# 04-ModuleControls.net
KiCad netlist of a schematic drawn in Altium Designer
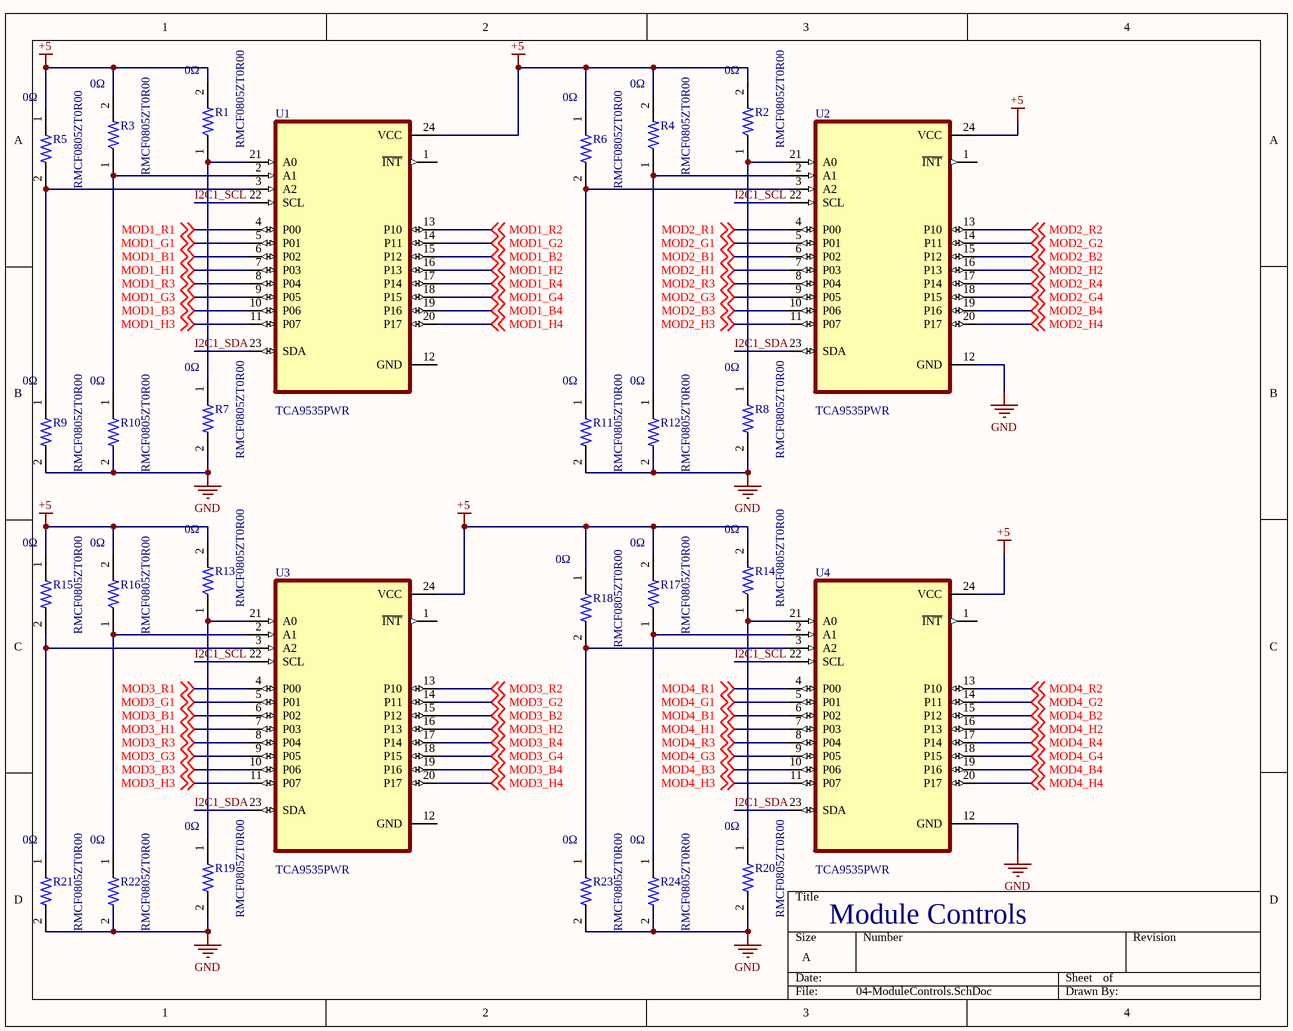
[diagram p0: 04-ModuleControls.SchDoc]

(export (version "E")
  (design (tool "Eeschema 10.0.6"))
  (components
    (comp (ref "R1")
      (value "RMCF0805ZT0R00")
      (footprint "RESC2012X60N")
      (description "0 Ohms Jumper 0.125W, 1/8W Chip Resistor 0805 (2012 Metric) Automotive AEC-Q200 Thick Film")
      (fields (field (name "MF") "Stackpole Electronics") (field (name "RESITANCE") "0Ω"))
      (libsource (lib "base-board") (part "RMCF0805ZT0R00"))
    )
    (comp (ref "R2")
      (value "RMCF0805ZT0R00")
      (footprint "RESC2012X60N")
      (description "0 Ohms Jumper 0.125W, 1/8W Chip Resistor 0805 (2012 Metric) Automotive AEC-Q200 Thick Film")
      (fields (field (name "MF") "Stackpole Electronics") (field (name "RESITANCE") "0Ω"))
      (libsource (lib "base-board") (part "RMCF0805ZT0R00"))
    )
    (comp (ref "R3")
      (value "RMCF0805ZT0R00")
      (footprint "RESC2012X60N")
      (description "0 Ohms Jumper 0.125W, 1/8W Chip Resistor 0805 (2012 Metric) Automotive AEC-Q200 Thick Film")
      (fields (field (name "MF") "Stackpole Electronics") (field (name "RESITANCE") "0Ω"))
      (libsource (lib "base-board") (part "RMCF0805ZT0R00"))
    )
    (comp (ref "R4")
      (value "RMCF0805ZT0R00")
      (footprint "RESC2012X60N")
      (description "0 Ohms Jumper 0.125W, 1/8W Chip Resistor 0805 (2012 Metric) Automotive AEC-Q200 Thick Film")
      (fields (field (name "MF") "Stackpole Electronics") (field (name "RESITANCE") "0Ω"))
      (libsource (lib "base-board") (part "RMCF0805ZT0R00"))
    )
    (comp (ref "R5")
      (value "RMCF0805ZT0R00")
      (footprint "RESC2012X60N")
      (description "0 Ohms Jumper 0.125W, 1/8W Chip Resistor 0805 (2012 Metric) Automotive AEC-Q200 Thick Film")
      (fields (field (name "MF") "Stackpole Electronics") (field (name "RESITANCE") "0Ω"))
      (libsource (lib "base-board") (part "RMCF0805ZT0R00"))
    )
    (comp (ref "R6")
      (value "RMCF0805ZT0R00")
      (footprint "RESC2012X60N")
      (description "0 Ohms Jumper 0.125W, 1/8W Chip Resistor 0805 (2012 Metric) Automotive AEC-Q200 Thick Film")
      (fields (field (name "MF") "Stackpole Electronics") (field (name "RESITANCE") "0Ω"))
      (libsource (lib "base-board") (part "RMCF0805ZT0R00"))
    )
    (comp (ref "R7")
      (value "RMCF0805ZT0R00")
      (footprint "RESC2012X60N")
      (description "0 Ohms Jumper 0.125W, 1/8W Chip Resistor 0805 (2012 Metric) Automotive AEC-Q200 Thick Film")
      (fields (field (name "MF") "Stackpole Electronics") (field (name "RESITANCE") "0Ω"))
      (libsource (lib "base-board") (part "RMCF0805ZT0R00"))
    )
    (comp (ref "R8")
      (value "RMCF0805ZT0R00")
      (footprint "RESC2012X60N")
      (description "0 Ohms Jumper 0.125W, 1/8W Chip Resistor 0805 (2012 Metric) Automotive AEC-Q200 Thick Film")
      (fields (field (name "MF") "Stackpole Electronics") (field (name "RESITANCE") "0Ω"))
      (libsource (lib "base-board") (part "RMCF0805ZT0R00"))
    )
    (comp (ref "R9")
      (value "RMCF0805ZT0R00")
      (footprint "RESC2012X60N")
      (description "0 Ohms Jumper 0.125W, 1/8W Chip Resistor 0805 (2012 Metric) Automotive AEC-Q200 Thick Film")
      (fields (field (name "MF") "Stackpole Electronics") (field (name "RESITANCE") "0Ω"))
      (libsource (lib "base-board") (part "RMCF0805ZT0R00"))
    )
    (comp (ref "R10")
      (value "RMCF0805ZT0R00")
      (footprint "RESC2012X60N")
      (description "0 Ohms Jumper 0.125W, 1/8W Chip Resistor 0805 (2012 Metric) Automotive AEC-Q200 Thick Film")
      (fields (field (name "MF") "Stackpole Electronics") (field (name "RESITANCE") "0Ω"))
      (libsource (lib "base-board") (part "RMCF0805ZT0R00"))
    )
    (comp (ref "R11")
      (value "RMCF0805ZT0R00")
      (footprint "RESC2012X60N")
      (description "0 Ohms Jumper 0.125W, 1/8W Chip Resistor 0805 (2012 Metric) Automotive AEC-Q200 Thick Film")
      (fields (field (name "MF") "Stackpole Electronics") (field (name "RESITANCE") "0Ω"))
      (libsource (lib "base-board") (part "RMCF0805ZT0R00"))
    )
    (comp (ref "R12")
      (value "RMCF0805ZT0R00")
      (footprint "RESC2012X60N")
      (description "0 Ohms Jumper 0.125W, 1/8W Chip Resistor 0805 (2012 Metric) Automotive AEC-Q200 Thick Film")
      (fields (field (name "MF") "Stackpole Electronics") (field (name "RESITANCE") "0Ω"))
      (libsource (lib "base-board") (part "RMCF0805ZT0R00"))
    )
    (comp (ref "R13")
      (value "RMCF0805ZT0R00")
      (footprint "RESC2012X60N")
      (description "0 Ohms Jumper 0.125W, 1/8W Chip Resistor 0805 (2012 Metric) Automotive AEC-Q200 Thick Film")
      (fields (field (name "MF") "Stackpole Electronics") (field (name "RESITANCE") "0Ω"))
      (libsource (lib "base-board") (part "RMCF0805ZT0R00"))
    )
    (comp (ref "R14")
      (value "RMCF0805ZT0R00")
      (footprint "RESC2012X60N")
      (description "0 Ohms Jumper 0.125W, 1/8W Chip Resistor 0805 (2012 Metric) Automotive AEC-Q200 Thick Film")
      (fields (field (name "MF") "Stackpole Electronics") (field (name "RESITANCE") "0Ω"))
      (libsource (lib "base-board") (part "RMCF0805ZT0R00"))
    )
    (comp (ref "R15")
      (value "RMCF0805ZT0R00")
      (footprint "RESC2012X60N")
      (description "0 Ohms Jumper 0.125W, 1/8W Chip Resistor 0805 (2012 Metric) Automotive AEC-Q200 Thick Film")
      (fields (field (name "MF") "Stackpole Electronics") (field (name "RESITANCE") "0Ω"))
      (libsource (lib "base-board") (part "RMCF0805ZT0R00"))
    )
    (comp (ref "R16")
      (value "RMCF0805ZT0R00")
      (footprint "RESC2012X60N")
      (description "0 Ohms Jumper 0.125W, 1/8W Chip Resistor 0805 (2012 Metric) Automotive AEC-Q200 Thick Film")
      (fields (field (name "MF") "Stackpole Electronics") (field (name "RESITANCE") "0Ω"))
      (libsource (lib "base-board") (part "RMCF0805ZT0R00"))
    )
    (comp (ref "R17")
      (value "RMCF0805ZT0R00")
      (footprint "RESC2012X60N")
      (description "0 Ohms Jumper 0.125W, 1/8W Chip Resistor 0805 (2012 Metric) Automotive AEC-Q200 Thick Film")
      (fields (field (name "MF") "Stackpole Electronics") (field (name "RESITANCE") "0Ω"))
      (libsource (lib "base-board") (part "RMCF0805ZT0R00"))
    )
    (comp (ref "R18")
      (value "RMCF0805ZT0R00")
      (footprint "RESC2012X60N")
      (description "0 Ohms Jumper 0.125W, 1/8W Chip Resistor 0805 (2012 Metric) Automotive AEC-Q200 Thick Film")
      (fields (field (name "MF") "Stackpole Electronics") (field (name "RESITANCE") "0Ω"))
      (libsource (lib "base-board") (part "RMCF0805ZT0R00"))
    )
    (comp (ref "R19")
      (value "RMCF0805ZT0R00")
      (footprint "RESC2012X60N")
      (description "0 Ohms Jumper 0.125W, 1/8W Chip Resistor 0805 (2012 Metric) Automotive AEC-Q200 Thick Film")
      (fields (field (name "MF") "Stackpole Electronics") (field (name "RESITANCE") "0Ω"))
      (libsource (lib "base-board") (part "RMCF0805ZT0R00"))
    )
    (comp (ref "R20")
      (value "RMCF0805ZT0R00")
      (footprint "RESC2012X60N")
      (description "0 Ohms Jumper 0.125W, 1/8W Chip Resistor 0805 (2012 Metric) Automotive AEC-Q200 Thick Film")
      (fields (field (name "MF") "Stackpole Electronics") (field (name "RESITANCE") "0Ω"))
      (libsource (lib "base-board") (part "RMCF0805ZT0R00"))
    )
    (comp (ref "R21")
      (value "RMCF0805ZT0R00")
      (footprint "RESC2012X60N")
      (description "0 Ohms Jumper 0.125W, 1/8W Chip Resistor 0805 (2012 Metric) Automotive AEC-Q200 Thick Film")
      (fields (field (name "MF") "Stackpole Electronics") (field (name "RESITANCE") "0Ω"))
      (libsource (lib "base-board") (part "RMCF0805ZT0R00"))
    )
    (comp (ref "R22")
      (value "RMCF0805ZT0R00")
      (footprint "RESC2012X60N")
      (description "0 Ohms Jumper 0.125W, 1/8W Chip Resistor 0805 (2012 Metric) Automotive AEC-Q200 Thick Film")
      (fields (field (name "MF") "Stackpole Electronics") (field (name "RESITANCE") "0Ω"))
      (libsource (lib "base-board") (part "RMCF0805ZT0R00"))
    )
    (comp (ref "R23")
      (value "RMCF0805ZT0R00")
      (footprint "RESC2012X60N")
      (description "0 Ohms Jumper 0.125W, 1/8W Chip Resistor 0805 (2012 Metric) Automotive AEC-Q200 Thick Film")
      (fields (field (name "MF") "Stackpole Electronics") (field (name "RESITANCE") "0Ω"))
      (libsource (lib "base-board") (part "RMCF0805ZT0R00"))
    )
    (comp (ref "R24")
      (value "RMCF0805ZT0R00")
      (footprint "RESC2012X60N")
      (description "0 Ohms Jumper 0.125W, 1/8W Chip Resistor 0805 (2012 Metric) Automotive AEC-Q200 Thick Film")
      (fields (field (name "MF") "Stackpole Electronics") (field (name "RESITANCE") "0Ω"))
      (libsource (lib "base-board") (part "RMCF0805ZT0R00"))
    )
    (comp (ref "U1")
      (value "TCA9535PWR")
      (footprint "SOP65P640X120-24N")
      (fields (field (name "MF") "Texas Instruments"))
      (libsource (lib "base-board") (part "TCA9535PWR"))
    )
    (comp (ref "U2")
      (value "TCA9535PWR")
      (footprint "SOP65P640X120-24N")
      (fields (field (name "MF") "Texas Instruments"))
      (libsource (lib "base-board") (part "TCA9535PWR"))
    )
    (comp (ref "U3")
      (value "TCA9535PWR")
      (footprint "SOP65P640X120-24N")
      (fields (field (name "MF") "Texas Instruments"))
      (libsource (lib "base-board") (part "TCA9535PWR"))
    )
    (comp (ref "U4")
      (value "TCA9535PWR")
      (footprint "SOP65P640X120-24N")
      (fields (field (name "MF") "Texas Instruments"))
      (libsource (lib "base-board") (part "TCA9535PWR"))
    )
  )
  (nets
    (net (code "1") (name "+5") (class "Default")
      (node (ref "R1") (pin "2") (pinfunction "2_2") (pintype "passive"))
      (node (ref "R13") (pin "2") (pinfunction "2_2") (pintype "passive"))
      (node (ref "R14") (pin "2") (pinfunction "2_2") (pintype "passive"))
      (node (ref "R15") (pin "1") (pinfunction "1_1") (pintype "passive"))
      (node (ref "R16") (pin "2") (pinfunction "2_2") (pintype "passive"))
      (node (ref "R17") (pin "2") (pinfunction "2_2") (pintype "passive"))
      (node (ref "R18") (pin "1") (pinfunction "1_1") (pintype "passive"))
      (node (ref "R2") (pin "2") (pinfunction "2_2") (pintype "passive"))
      (node (ref "R3") (pin "2") (pinfunction "2_2") (pintype "passive"))
      (node (ref "R4") (pin "2") (pinfunction "2_2") (pintype "passive"))
      (node (ref "R5") (pin "1") (pinfunction "1_1") (pintype "passive"))
      (node (ref "R6") (pin "1") (pinfunction "1_1") (pintype "passive"))
      (node (ref "U1") (pin "24") (pinfunction "VCC_24") (pintype "power_in"))
      (node (ref "U2") (pin "24") (pinfunction "VCC_24") (pintype "power_in"))
      (node (ref "U3") (pin "24") (pinfunction "VCC_24") (pintype "power_in"))
      (node (ref "U4") (pin "24") (pinfunction "VCC_24") (pintype "power_in"))
    )
    (net (code "2") (name "/I2C1_SCL") (class "Default")
      (node (ref "U1") (pin "22") (pinfunction "SCL_22") (pintype "input"))
      (node (ref "U2") (pin "22") (pinfunction "SCL_22") (pintype "input"))
      (node (ref "U3") (pin "22") (pinfunction "SCL_22") (pintype "input"))
      (node (ref "U4") (pin "22") (pinfunction "SCL_22") (pintype "input"))
    )
    (net (code "3") (name "/I2C1_SDA") (class "Default")
      (node (ref "U1") (pin "23") (pinfunction "SDA_23") (pintype "bidirectional"))
      (node (ref "U2") (pin "23") (pinfunction "SDA_23") (pintype "bidirectional"))
      (node (ref "U3") (pin "23") (pinfunction "SDA_23") (pintype "bidirectional"))
      (node (ref "U4") (pin "23") (pinfunction "SDA_23") (pintype "bidirectional"))
    )
    (net (code "4") (name "GND") (class "Default")
      (node (ref "R10") (pin "2") (pinfunction "2_2") (pintype "passive"))
      (node (ref "R11") (pin "2") (pinfunction "2_2") (pintype "passive"))
      (node (ref "R12") (pin "2") (pinfunction "2_2") (pintype "passive"))
      (node (ref "R19") (pin "2") (pinfunction "2_2") (pintype "passive"))
      (node (ref "R20") (pin "2") (pinfunction "2_2") (pintype "passive"))
      (node (ref "R21") (pin "2") (pinfunction "2_2") (pintype "passive"))
      (node (ref "R22") (pin "2") (pinfunction "2_2") (pintype "passive"))
      (node (ref "R23") (pin "2") (pinfunction "2_2") (pintype "passive"))
      (node (ref "R24") (pin "2") (pinfunction "2_2") (pintype "passive"))
      (node (ref "R7") (pin "2") (pinfunction "2_2") (pintype "passive"))
      (node (ref "R8") (pin "2") (pinfunction "2_2") (pintype "passive"))
      (node (ref "R9") (pin "2") (pinfunction "2_2") (pintype "passive"))
      (node (ref "U2") (pin "12") (pinfunction "GND_12") (pintype "power_in"))
      (node (ref "U4") (pin "12") (pinfunction "GND_12") (pintype "power_in"))
    )
    (net (code "5") (name "MOD1_B1") (class "Default")
      (node (ref "U1") (pin "6") (pinfunction "P02_6") (pintype "bidirectional"))
    )
    (net (code "6") (name "MOD1_B2") (class "Default")
      (node (ref "U1") (pin "15") (pinfunction "P12_15") (pintype "bidirectional"))
    )
    (net (code "7") (name "MOD1_B3") (class "Default")
      (node (ref "U1") (pin "10") (pinfunction "P06_10") (pintype "bidirectional"))
    )
    (net (code "8") (name "MOD1_B4") (class "Default")
      (node (ref "U1") (pin "19") (pinfunction "P16_19") (pintype "bidirectional"))
    )
    (net (code "9") (name "MOD1_G1") (class "Default")
      (node (ref "U1") (pin "5") (pinfunction "P01_5") (pintype "bidirectional"))
    )
    (net (code "10") (name "MOD1_G2") (class "Default")
      (node (ref "U1") (pin "14") (pinfunction "P11_14") (pintype "bidirectional"))
    )
    (net (code "11") (name "MOD1_G3") (class "Default")
      (node (ref "U1") (pin "9") (pinfunction "P05_9") (pintype "bidirectional"))
    )
    (net (code "12") (name "MOD1_G4") (class "Default")
      (node (ref "U1") (pin "18") (pinfunction "P15_18") (pintype "bidirectional"))
    )
    (net (code "13") (name "MOD1_H1") (class "Default")
      (node (ref "U1") (pin "7") (pinfunction "P03_7") (pintype "bidirectional"))
    )
    (net (code "14") (name "MOD1_H2") (class "Default")
      (node (ref "U1") (pin "16") (pinfunction "P13_16") (pintype "bidirectional"))
    )
    (net (code "15") (name "MOD1_H3") (class "Default")
      (node (ref "U1") (pin "11") (pinfunction "P07_11") (pintype "bidirectional"))
    )
    (net (code "16") (name "MOD1_H4") (class "Default")
      (node (ref "U1") (pin "20") (pinfunction "P17_20") (pintype "bidirectional"))
    )
    (net (code "17") (name "MOD1_R1") (class "Default")
      (node (ref "U1") (pin "4") (pinfunction "P00_4") (pintype "bidirectional"))
    )
    (net (code "18") (name "MOD1_R2") (class "Default")
      (node (ref "U1") (pin "13") (pinfunction "P10_13") (pintype "bidirectional"))
    )
    (net (code "19") (name "MOD1_R3") (class "Default")
      (node (ref "U1") (pin "8") (pinfunction "P04_8") (pintype "bidirectional"))
    )
    (net (code "20") (name "MOD1_R4") (class "Default")
      (node (ref "U1") (pin "17") (pinfunction "P14_17") (pintype "bidirectional"))
    )
    (net (code "21") (name "MOD2_B1") (class "Default")
      (node (ref "U2") (pin "6") (pinfunction "P02_6") (pintype "bidirectional"))
    )
    (net (code "22") (name "MOD2_B2") (class "Default")
      (node (ref "U2") (pin "15") (pinfunction "P12_15") (pintype "bidirectional"))
    )
    (net (code "23") (name "MOD2_B3") (class "Default")
      (node (ref "U2") (pin "10") (pinfunction "P06_10") (pintype "bidirectional"))
    )
    (net (code "24") (name "MOD2_B4") (class "Default")
      (node (ref "U2") (pin "19") (pinfunction "P16_19") (pintype "bidirectional"))
    )
    (net (code "25") (name "MOD2_G1") (class "Default")
      (node (ref "U2") (pin "5") (pinfunction "P01_5") (pintype "bidirectional"))
    )
    (net (code "26") (name "MOD2_G2") (class "Default")
      (node (ref "U2") (pin "14") (pinfunction "P11_14") (pintype "bidirectional"))
    )
    (net (code "27") (name "MOD2_G3") (class "Default")
      (node (ref "U2") (pin "9") (pinfunction "P05_9") (pintype "bidirectional"))
    )
    (net (code "28") (name "MOD2_G4") (class "Default")
      (node (ref "U2") (pin "18") (pinfunction "P15_18") (pintype "bidirectional"))
    )
    (net (code "29") (name "MOD2_H1") (class "Default")
      (node (ref "U2") (pin "7") (pinfunction "P03_7") (pintype "bidirectional"))
    )
    (net (code "30") (name "MOD2_H2") (class "Default")
      (node (ref "U2") (pin "16") (pinfunction "P13_16") (pintype "bidirectional"))
    )
    (net (code "31") (name "MOD2_H3") (class "Default")
      (node (ref "U2") (pin "11") (pinfunction "P07_11") (pintype "bidirectional"))
    )
    (net (code "32") (name "MOD2_H4") (class "Default")
      (node (ref "U2") (pin "20") (pinfunction "P17_20") (pintype "bidirectional"))
    )
    (net (code "33") (name "MOD2_R1") (class "Default")
      (node (ref "U2") (pin "4") (pinfunction "P00_4") (pintype "bidirectional"))
    )
    (net (code "34") (name "MOD2_R2") (class "Default")
      (node (ref "U2") (pin "13") (pinfunction "P10_13") (pintype "bidirectional"))
    )
    (net (code "35") (name "MOD2_R3") (class "Default")
      (node (ref "U2") (pin "8") (pinfunction "P04_8") (pintype "bidirectional"))
    )
    (net (code "36") (name "MOD2_R4") (class "Default")
      (node (ref "U2") (pin "17") (pinfunction "P14_17") (pintype "bidirectional"))
    )
    (net (code "37") (name "MOD3_B1") (class "Default")
      (node (ref "U3") (pin "6") (pinfunction "P02_6") (pintype "bidirectional"))
    )
    (net (code "38") (name "MOD3_B2") (class "Default")
      (node (ref "U3") (pin "15") (pinfunction "P12_15") (pintype "bidirectional"))
    )
    (net (code "39") (name "MOD3_B3") (class "Default")
      (node (ref "U3") (pin "10") (pinfunction "P06_10") (pintype "bidirectional"))
    )
    (net (code "40") (name "MOD3_B4") (class "Default")
      (node (ref "U3") (pin "19") (pinfunction "P16_19") (pintype "bidirectional"))
    )
    (net (code "41") (name "MOD3_G1") (class "Default")
      (node (ref "U3") (pin "5") (pinfunction "P01_5") (pintype "bidirectional"))
    )
    (net (code "42") (name "MOD3_G2") (class "Default")
      (node (ref "U3") (pin "14") (pinfunction "P11_14") (pintype "bidirectional"))
    )
    (net (code "43") (name "MOD3_G3") (class "Default")
      (node (ref "U3") (pin "9") (pinfunction "P05_9") (pintype "bidirectional"))
    )
    (net (code "44") (name "MOD3_G4") (class "Default")
      (node (ref "U3") (pin "18") (pinfunction "P15_18") (pintype "bidirectional"))
    )
    (net (code "45") (name "MOD3_H1") (class "Default")
      (node (ref "U3") (pin "7") (pinfunction "P03_7") (pintype "bidirectional"))
    )
    (net (code "46") (name "MOD3_H2") (class "Default")
      (node (ref "U3") (pin "16") (pinfunction "P13_16") (pintype "bidirectional"))
    )
    (net (code "47") (name "MOD3_H3") (class "Default")
      (node (ref "U3") (pin "11") (pinfunction "P07_11") (pintype "bidirectional"))
    )
    (net (code "48") (name "MOD3_H4") (class "Default")
      (node (ref "U3") (pin "20") (pinfunction "P17_20") (pintype "bidirectional"))
    )
    (net (code "49") (name "MOD3_R1") (class "Default")
      (node (ref "U3") (pin "4") (pinfunction "P00_4") (pintype "bidirectional"))
    )
    (net (code "50") (name "MOD3_R2") (class "Default")
      (node (ref "U3") (pin "13") (pinfunction "P10_13") (pintype "bidirectional"))
    )
    (net (code "51") (name "MOD3_R3") (class "Default")
      (node (ref "U3") (pin "8") (pinfunction "P04_8") (pintype "bidirectional"))
    )
    (net (code "52") (name "MOD3_R4") (class "Default")
      (node (ref "U3") (pin "17") (pinfunction "P14_17") (pintype "bidirectional"))
    )
    (net (code "53") (name "MOD4_B1") (class "Default")
      (node (ref "U4") (pin "6") (pinfunction "P02_6") (pintype "bidirectional"))
    )
    (net (code "54") (name "MOD4_B2") (class "Default")
      (node (ref "U4") (pin "15") (pinfunction "P12_15") (pintype "bidirectional"))
    )
    (net (code "55") (name "MOD4_B3") (class "Default")
      (node (ref "U4") (pin "10") (pinfunction "P06_10") (pintype "bidirectional"))
    )
    (net (code "56") (name "MOD4_B4") (class "Default")
      (node (ref "U4") (pin "19") (pinfunction "P16_19") (pintype "bidirectional"))
    )
    (net (code "57") (name "MOD4_G1") (class "Default")
      (node (ref "U4") (pin "5") (pinfunction "P01_5") (pintype "bidirectional"))
    )
    (net (code "58") (name "MOD4_G2") (class "Default")
      (node (ref "U4") (pin "14") (pinfunction "P11_14") (pintype "bidirectional"))
    )
    (net (code "59") (name "MOD4_G3") (class "Default")
      (node (ref "U4") (pin "9") (pinfunction "P05_9") (pintype "bidirectional"))
    )
    (net (code "60") (name "MOD4_G4") (class "Default")
      (node (ref "U4") (pin "18") (pinfunction "P15_18") (pintype "bidirectional"))
    )
    (net (code "61") (name "MOD4_H1") (class "Default")
      (node (ref "U4") (pin "7") (pinfunction "P03_7") (pintype "bidirectional"))
    )
    (net (code "62") (name "MOD4_H2") (class "Default")
      (node (ref "U4") (pin "16") (pinfunction "P13_16") (pintype "bidirectional"))
    )
    (net (code "63") (name "MOD4_H3") (class "Default")
      (node (ref "U4") (pin "11") (pinfunction "P07_11") (pintype "bidirectional"))
    )
    (net (code "64") (name "MOD4_H4") (class "Default")
      (node (ref "U4") (pin "20") (pinfunction "P17_20") (pintype "bidirectional"))
    )
    (net (code "65") (name "MOD4_R1") (class "Default")
      (node (ref "U4") (pin "4") (pinfunction "P00_4") (pintype "bidirectional"))
    )
    (net (code "66") (name "MOD4_R2") (class "Default")
      (node (ref "U4") (pin "13") (pinfunction "P10_13") (pintype "bidirectional"))
    )
    (net (code "67") (name "MOD4_R3") (class "Default")
      (node (ref "U4") (pin "8") (pinfunction "P04_8") (pintype "bidirectional"))
    )
    (net (code "68") (name "MOD4_R4") (class "Default")
      (node (ref "U4") (pin "17") (pinfunction "P14_17") (pintype "bidirectional"))
    )
    (net (code "69") (name "Net-(U1-A0)") (class "Default")
      (node (ref "R1") (pin "1") (pinfunction "1_1") (pintype "passive"))
      (node (ref "R7") (pin "1") (pinfunction "1_1") (pintype "passive"))
      (node (ref "U1") (pin "21") (pinfunction "A0_21") (pintype "input"))
    )
    (net (code "70") (name "Net-(U1-A1)") (class "Default")
      (node (ref "R10") (pin "1") (pinfunction "1_1") (pintype "passive"))
      (node (ref "R3") (pin "1") (pinfunction "1_1") (pintype "passive"))
      (node (ref "U1") (pin "2") (pinfunction "A1_2") (pintype "input"))
    )
    (net (code "71") (name "Net-(U1-A2)") (class "Default")
      (node (ref "R5") (pin "2") (pinfunction "2_2") (pintype "passive"))
      (node (ref "R9") (pin "1") (pinfunction "1_1") (pintype "passive"))
      (node (ref "U1") (pin "3") (pinfunction "A2_3") (pintype "input"))
    )
    (net (code "72") (name "Net-(U2-A0)") (class "Default")
      (node (ref "R2") (pin "1") (pinfunction "1_1") (pintype "passive"))
      (node (ref "R8") (pin "1") (pinfunction "1_1") (pintype "passive"))
      (node (ref "U2") (pin "21") (pinfunction "A0_21") (pintype "input"))
    )
    (net (code "73") (name "Net-(U2-A1)") (class "Default")
      (node (ref "R12") (pin "1") (pinfunction "1_1") (pintype "passive"))
      (node (ref "R4") (pin "1") (pinfunction "1_1") (pintype "passive"))
      (node (ref "U2") (pin "2") (pinfunction "A1_2") (pintype "input"))
    )
    (net (code "74") (name "Net-(U2-A2)") (class "Default")
      (node (ref "R11") (pin "1") (pinfunction "1_1") (pintype "passive"))
      (node (ref "R6") (pin "2") (pinfunction "2_2") (pintype "passive"))
      (node (ref "U2") (pin "3") (pinfunction "A2_3") (pintype "input"))
    )
    (net (code "75") (name "Net-(U3-A0)") (class "Default")
      (node (ref "R13") (pin "1") (pinfunction "1_1") (pintype "passive"))
      (node (ref "R19") (pin "1") (pinfunction "1_1") (pintype "passive"))
      (node (ref "U3") (pin "21") (pinfunction "A0_21") (pintype "input"))
    )
    (net (code "76") (name "Net-(U3-A1)") (class "Default")
      (node (ref "R16") (pin "1") (pinfunction "1_1") (pintype "passive"))
      (node (ref "R22") (pin "1") (pinfunction "1_1") (pintype "passive"))
      (node (ref "U3") (pin "2") (pinfunction "A1_2") (pintype "input"))
    )
    (net (code "77") (name "Net-(U3-A2)") (class "Default")
      (node (ref "R15") (pin "2") (pinfunction "2_2") (pintype "passive"))
      (node (ref "R21") (pin "1") (pinfunction "1_1") (pintype "passive"))
      (node (ref "U3") (pin "3") (pinfunction "A2_3") (pintype "input"))
    )
    (net (code "78") (name "Net-(U4-A0)") (class "Default")
      (node (ref "R14") (pin "1") (pinfunction "1_1") (pintype "passive"))
      (node (ref "R20") (pin "1") (pinfunction "1_1") (pintype "passive"))
      (node (ref "U4") (pin "21") (pinfunction "A0_21") (pintype "input"))
    )
    (net (code "79") (name "Net-(U4-A1)") (class "Default")
      (node (ref "R17") (pin "1") (pinfunction "1_1") (pintype "passive"))
      (node (ref "R24") (pin "1") (pinfunction "1_1") (pintype "passive"))
      (node (ref "U4") (pin "2") (pinfunction "A1_2") (pintype "input"))
    )
    (net (code "80") (name "Net-(U4-A2)") (class "Default")
      (node (ref "R18") (pin "2") (pinfunction "2_2") (pintype "passive"))
      (node (ref "R23") (pin "1") (pinfunction "1_1") (pintype "passive"))
      (node (ref "U4") (pin "3") (pinfunction "A2_3") (pintype "input"))
    )
    (net (code "81") (name "unconnected-(U1-GND-Pad12)") (class "Default")
      (node (ref "U1") (pin "12") (pinfunction "GND_12") (pintype "power_in"))
    )
    (net (code "82") (name "unconnected-(U1-~{INT}-Pad1)") (class "Default")
      (node (ref "U1") (pin "1") (pinfunction "~{INT}_1") (pintype "output"))
    )
    (net (code "83") (name "unconnected-(U2-~{INT}-Pad1)") (class "Default")
      (node (ref "U2") (pin "1") (pinfunction "~{INT}_1") (pintype "output"))
    )
    (net (code "84") (name "unconnected-(U3-GND-Pad12)") (class "Default")
      (node (ref "U3") (pin "12") (pinfunction "GND_12") (pintype "power_in"))
    )
    (net (code "85") (name "unconnected-(U3-~{INT}-Pad1)") (class "Default")
      (node (ref "U3") (pin "1") (pinfunction "~{INT}_1") (pintype "output"))
    )
    (net (code "86") (name "unconnected-(U4-~{INT}-Pad1)") (class "Default")
      (node (ref "U4") (pin "1") (pinfunction "~{INT}_1") (pintype "output"))
    )
  )
)
